# V9.net
KiCad netlist of a schematic drawn in EAGLE
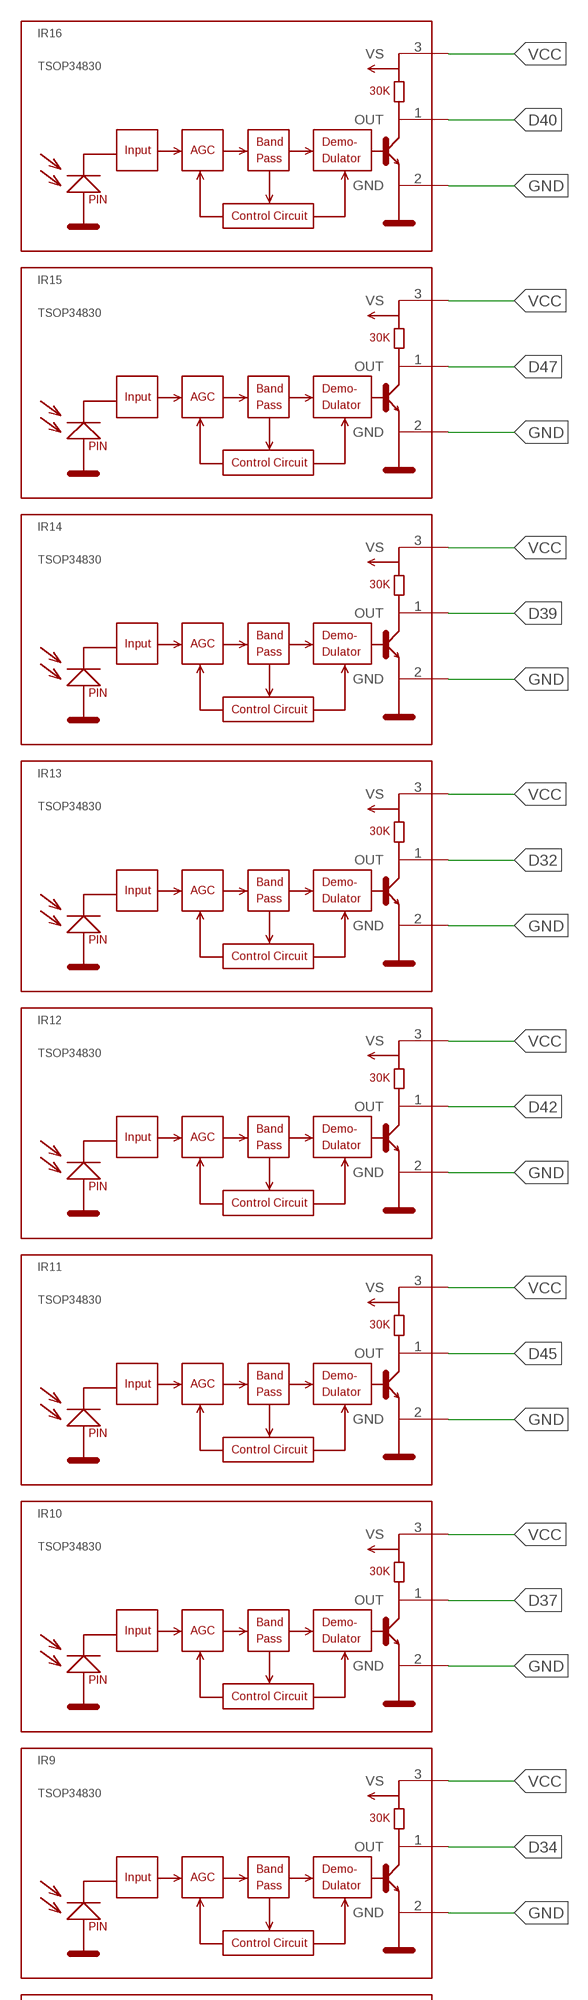
[diagram p0: schematic, sheet 1, part 1 of 2]
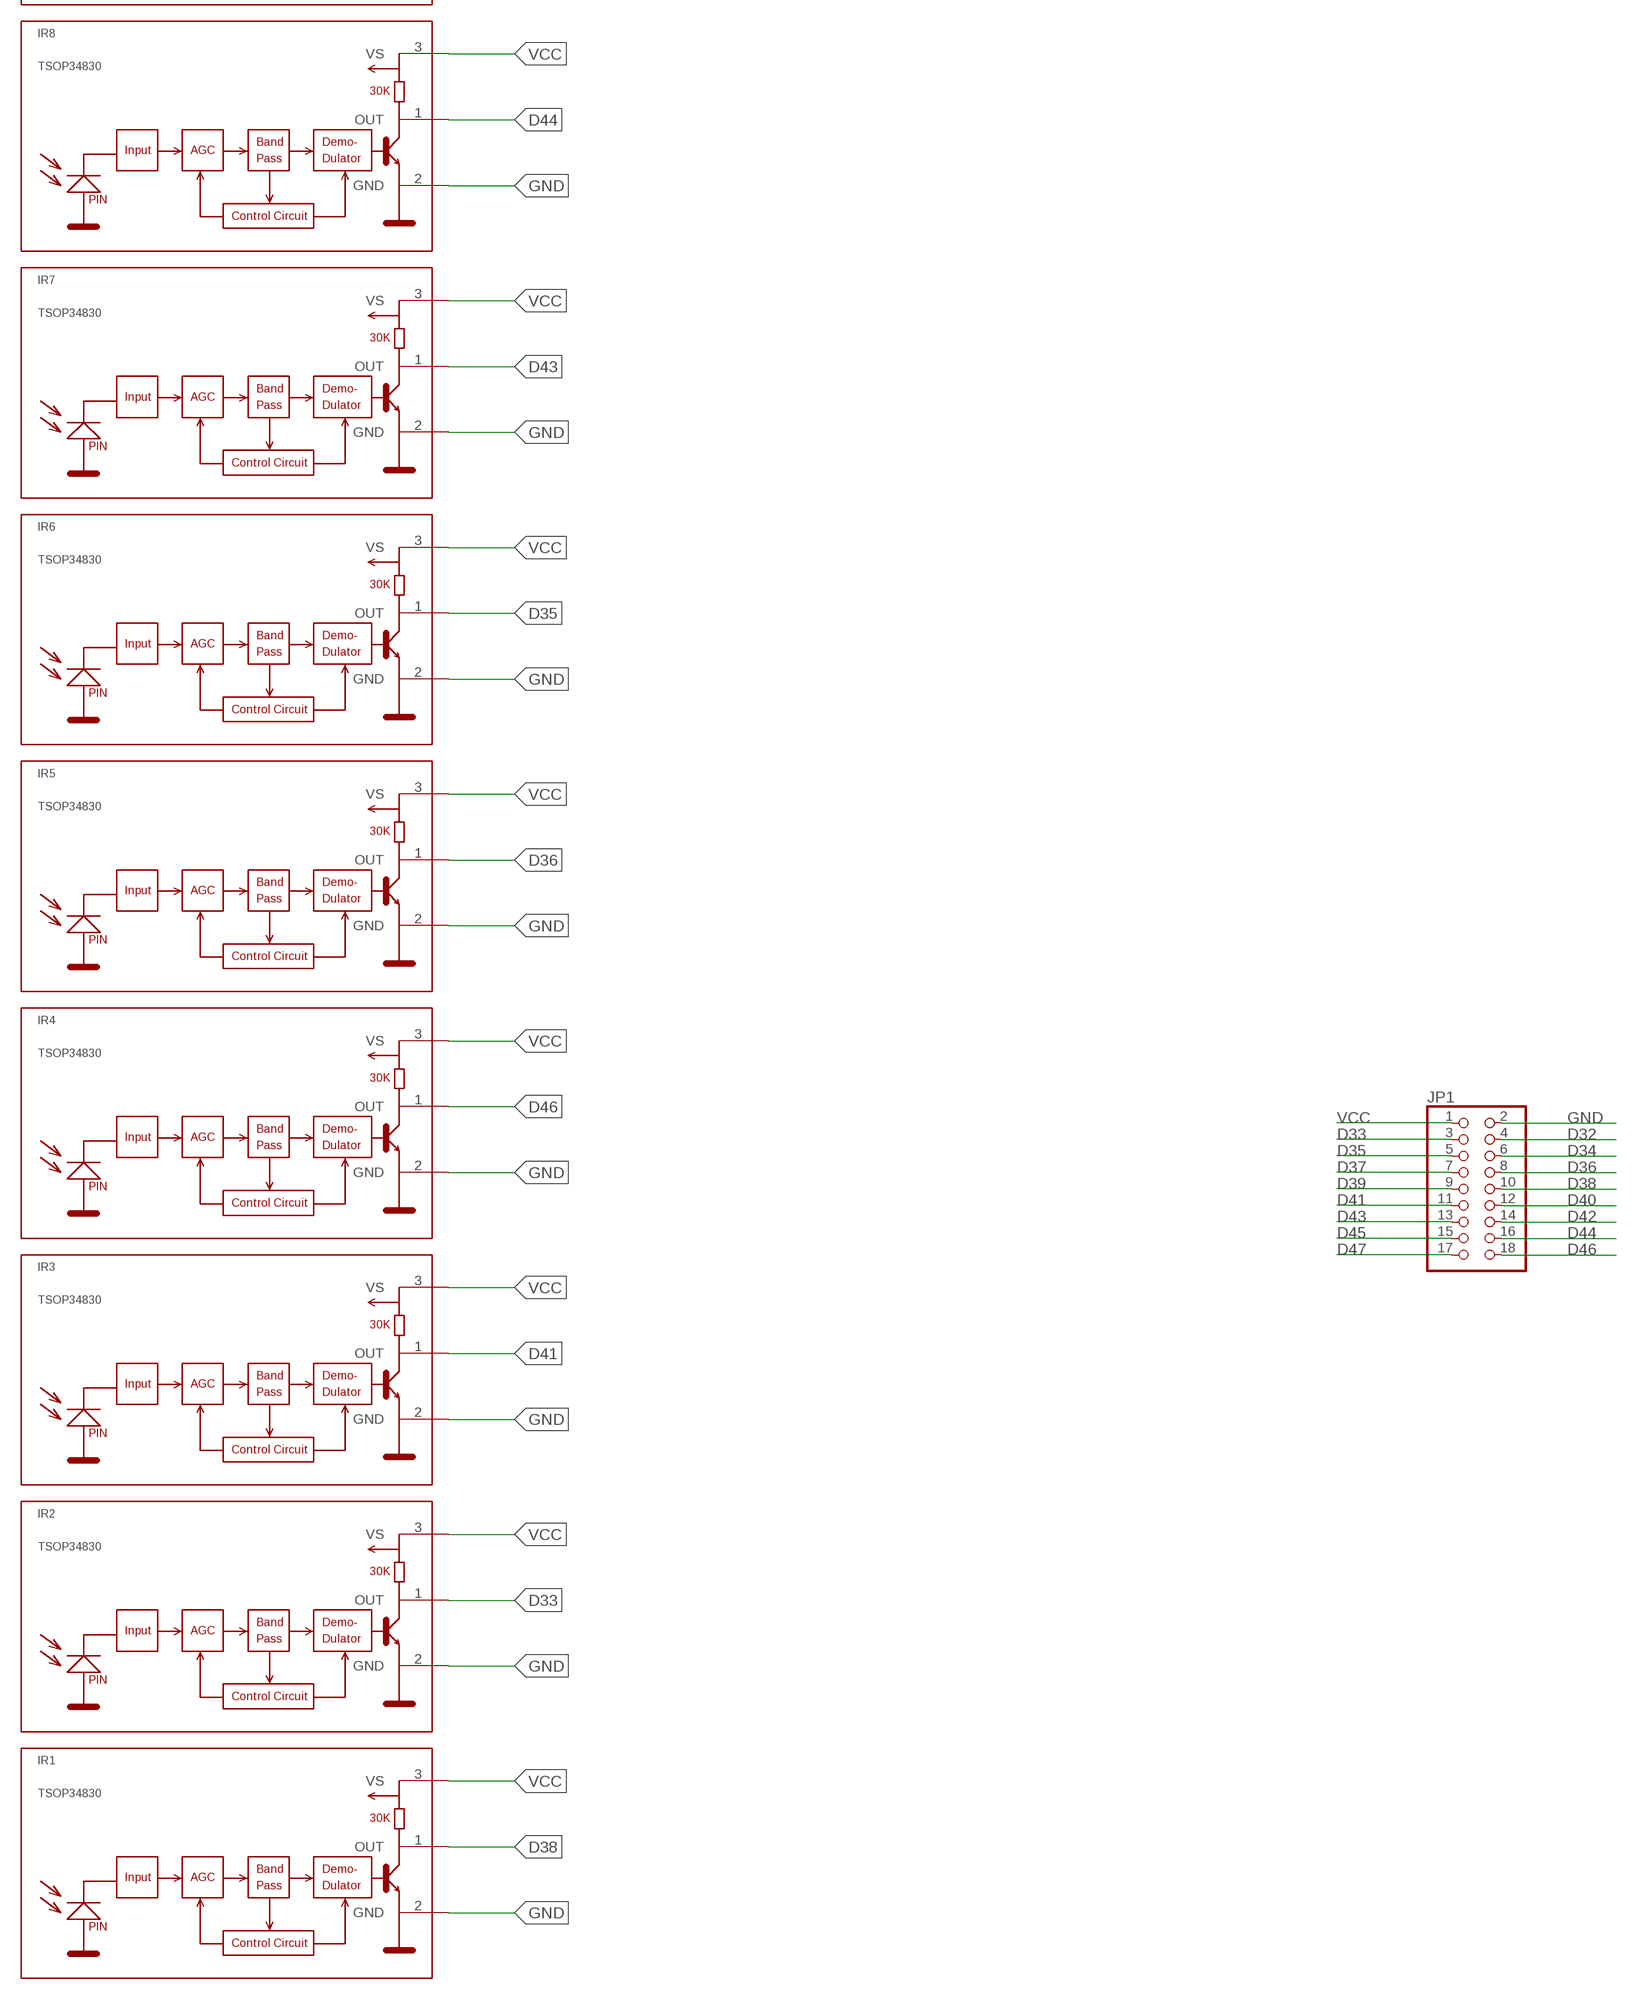
[diagram p1: schematic, sheet 1, part 2 of 2]

(export (version "E")
  (design (tool "Eeschema 10.0.6"))
  (components
    (comp (ref "IR1")
      (value "TSOP34830")
      (footprint "eagle-import:TSOP348")
      (libsource (lib "eagle-import") (part "TSOP34830"))
    )
    (comp (ref "IR2")
      (value "TSOP34830")
      (footprint "eagle-import:TSOP348")
      (libsource (lib "eagle-import") (part "TSOP34830"))
    )
    (comp (ref "IR3")
      (value "TSOP34830")
      (footprint "eagle-import:TSOP348")
      (libsource (lib "eagle-import") (part "TSOP34830"))
    )
    (comp (ref "IR4")
      (value "TSOP34830")
      (footprint "eagle-import:TSOP348")
      (libsource (lib "eagle-import") (part "TSOP34830"))
    )
    (comp (ref "IR5")
      (value "TSOP34830")
      (footprint "eagle-import:TSOP348")
      (libsource (lib "eagle-import") (part "TSOP34830"))
    )
    (comp (ref "IR6")
      (value "TSOP34830")
      (footprint "eagle-import:TSOP348")
      (libsource (lib "eagle-import") (part "TSOP34830"))
    )
    (comp (ref "IR7")
      (value "TSOP34830")
      (footprint "eagle-import:TSOP348")
      (libsource (lib "eagle-import") (part "TSOP34830"))
    )
    (comp (ref "IR8")
      (value "TSOP34830")
      (footprint "eagle-import:TSOP348")
      (libsource (lib "eagle-import") (part "TSOP34830"))
    )
    (comp (ref "IR9")
      (value "TSOP34830")
      (footprint "eagle-import:TSOP348")
      (libsource (lib "eagle-import") (part "TSOP34830"))
    )
    (comp (ref "IR10")
      (value "TSOP34830")
      (footprint "eagle-import:TSOP348")
      (libsource (lib "eagle-import") (part "TSOP34830"))
    )
    (comp (ref "IR11")
      (value "TSOP34830")
      (footprint "eagle-import:TSOP348")
      (libsource (lib "eagle-import") (part "TSOP34830"))
    )
    (comp (ref "IR12")
      (value "TSOP34830")
      (footprint "eagle-import:TSOP348")
      (libsource (lib "eagle-import") (part "TSOP34830"))
    )
    (comp (ref "IR13")
      (value "TSOP34830")
      (footprint "eagle-import:TSOP348")
      (libsource (lib "eagle-import") (part "TSOP34830"))
    )
    (comp (ref "IR14")
      (value "TSOP34830")
      (footprint "eagle-import:TSOP348")
      (libsource (lib "eagle-import") (part "TSOP34830"))
    )
    (comp (ref "IR15")
      (value "TSOP34830")
      (footprint "eagle-import:TSOP348")
      (libsource (lib "eagle-import") (part "TSOP34830"))
    )
    (comp (ref "IR16")
      (value "TSOP34830")
      (footprint "eagle-import:TSOP348")
      (libsource (lib "eagle-import") (part "TSOP34830"))
    )
    (comp (ref "JP1")
      (value "PINHD-2X09_2.54")
      (footprint "eagle-import:2X09")
      (libsource (lib "eagle-import") (part "PINHD-2X09_2.54"))
    )
  )
  (nets
    (net (code "1") (name "D32") (class "Default")
      (node (ref "IR13") (pin "1") (pinfunction "OUT_1") (pintype "output"))
      (node (ref "JP1") (pin "4") (pinfunction "4_4") (pintype "passive"))
    )
    (net (code "2") (name "D33") (class "Default")
      (node (ref "IR2") (pin "1") (pinfunction "OUT_1") (pintype "output"))
      (node (ref "JP1") (pin "3") (pinfunction "3_3") (pintype "passive"))
    )
    (net (code "3") (name "D34") (class "Default")
      (node (ref "IR9") (pin "1") (pinfunction "OUT_1") (pintype "output"))
      (node (ref "JP1") (pin "6") (pinfunction "6_6") (pintype "passive"))
    )
    (net (code "4") (name "D35") (class "Default")
      (node (ref "IR6") (pin "1") (pinfunction "OUT_1") (pintype "output"))
      (node (ref "JP1") (pin "5") (pinfunction "5_5") (pintype "passive"))
    )
    (net (code "5") (name "D36") (class "Default")
      (node (ref "IR5") (pin "1") (pinfunction "OUT_1") (pintype "output"))
      (node (ref "JP1") (pin "8") (pinfunction "8_8") (pintype "passive"))
    )
    (net (code "6") (name "D37") (class "Default")
      (node (ref "IR10") (pin "1") (pinfunction "OUT_1") (pintype "output"))
      (node (ref "JP1") (pin "7") (pinfunction "7_7") (pintype "passive"))
    )
    (net (code "7") (name "D38") (class "Default")
      (node (ref "IR1") (pin "1") (pinfunction "OUT_1") (pintype "output"))
      (node (ref "JP1") (pin "10") (pinfunction "10_10") (pintype "passive"))
    )
    (net (code "8") (name "D39") (class "Default")
      (node (ref "IR14") (pin "1") (pinfunction "OUT_1") (pintype "output"))
      (node (ref "JP1") (pin "9") (pinfunction "9_9") (pintype "passive"))
    )
    (net (code "9") (name "D40") (class "Default")
      (node (ref "IR16") (pin "1") (pinfunction "OUT_1") (pintype "output"))
      (node (ref "JP1") (pin "12") (pinfunction "12_12") (pintype "passive"))
    )
    (net (code "10") (name "D41") (class "Default")
      (node (ref "IR3") (pin "1") (pinfunction "OUT_1") (pintype "output"))
      (node (ref "JP1") (pin "11") (pinfunction "11_11") (pintype "passive"))
    )
    (net (code "11") (name "D42") (class "Default")
      (node (ref "IR12") (pin "1") (pinfunction "OUT_1") (pintype "output"))
      (node (ref "JP1") (pin "14") (pinfunction "14_14") (pintype "passive"))
    )
    (net (code "12") (name "D43") (class "Default")
      (node (ref "IR7") (pin "1") (pinfunction "OUT_1") (pintype "output"))
      (node (ref "JP1") (pin "13") (pinfunction "13_13") (pintype "passive"))
    )
    (net (code "13") (name "D44") (class "Default")
      (node (ref "IR8") (pin "1") (pinfunction "OUT_1") (pintype "output"))
      (node (ref "JP1") (pin "16") (pinfunction "16_16") (pintype "passive"))
    )
    (net (code "14") (name "D45") (class "Default")
      (node (ref "IR11") (pin "1") (pinfunction "OUT_1") (pintype "output"))
      (node (ref "JP1") (pin "15") (pinfunction "15_15") (pintype "passive"))
    )
    (net (code "15") (name "D46") (class "Default")
      (node (ref "IR4") (pin "1") (pinfunction "OUT_1") (pintype "output"))
      (node (ref "JP1") (pin "18") (pinfunction "18_18") (pintype "passive"))
    )
    (net (code "16") (name "D47") (class "Default")
      (node (ref "IR15") (pin "1") (pinfunction "OUT_1") (pintype "output"))
      (node (ref "JP1") (pin "17") (pinfunction "17_17") (pintype "passive"))
    )
    (net (code "17") (name "GND") (class "Default")
      (node (ref "IR1") (pin "2") (pinfunction "GND_2") (pintype "power_in"))
      (node (ref "IR10") (pin "2") (pinfunction "GND_2") (pintype "power_in"))
      (node (ref "IR11") (pin "2") (pinfunction "GND_2") (pintype "power_in"))
      (node (ref "IR12") (pin "2") (pinfunction "GND_2") (pintype "power_in"))
      (node (ref "IR13") (pin "2") (pinfunction "GND_2") (pintype "power_in"))
      (node (ref "IR14") (pin "2") (pinfunction "GND_2") (pintype "power_in"))
      (node (ref "IR15") (pin "2") (pinfunction "GND_2") (pintype "power_in"))
      (node (ref "IR16") (pin "2") (pinfunction "GND_2") (pintype "power_in"))
      (node (ref "IR2") (pin "2") (pinfunction "GND_2") (pintype "power_in"))
      (node (ref "IR3") (pin "2") (pinfunction "GND_2") (pintype "power_in"))
      (node (ref "IR4") (pin "2") (pinfunction "GND_2") (pintype "power_in"))
      (node (ref "IR5") (pin "2") (pinfunction "GND_2") (pintype "power_in"))
      (node (ref "IR6") (pin "2") (pinfunction "GND_2") (pintype "power_in"))
      (node (ref "IR7") (pin "2") (pinfunction "GND_2") (pintype "power_in"))
      (node (ref "IR8") (pin "2") (pinfunction "GND_2") (pintype "power_in"))
      (node (ref "IR9") (pin "2") (pinfunction "GND_2") (pintype "power_in"))
      (node (ref "JP1") (pin "2") (pinfunction "2_2") (pintype "passive"))
    )
    (net (code "18") (name "VCC") (class "Default")
      (node (ref "IR1") (pin "3") (pinfunction "VS_3") (pintype "power_in"))
      (node (ref "IR10") (pin "3") (pinfunction "VS_3") (pintype "power_in"))
      (node (ref "IR11") (pin "3") (pinfunction "VS_3") (pintype "power_in"))
      (node (ref "IR12") (pin "3") (pinfunction "VS_3") (pintype "power_in"))
      (node (ref "IR13") (pin "3") (pinfunction "VS_3") (pintype "power_in"))
      (node (ref "IR14") (pin "3") (pinfunction "VS_3") (pintype "power_in"))
      (node (ref "IR15") (pin "3") (pinfunction "VS_3") (pintype "power_in"))
      (node (ref "IR16") (pin "3") (pinfunction "VS_3") (pintype "power_in"))
      (node (ref "IR2") (pin "3") (pinfunction "VS_3") (pintype "power_in"))
      (node (ref "IR3") (pin "3") (pinfunction "VS_3") (pintype "power_in"))
      (node (ref "IR4") (pin "3") (pinfunction "VS_3") (pintype "power_in"))
      (node (ref "IR5") (pin "3") (pinfunction "VS_3") (pintype "power_in"))
      (node (ref "IR6") (pin "3") (pinfunction "VS_3") (pintype "power_in"))
      (node (ref "IR7") (pin "3") (pinfunction "VS_3") (pintype "power_in"))
      (node (ref "IR8") (pin "3") (pinfunction "VS_3") (pintype "power_in"))
      (node (ref "IR9") (pin "3") (pinfunction "VS_3") (pintype "power_in"))
      (node (ref "JP1") (pin "1") (pinfunction "1_1") (pintype "passive"))
    )
  )
)
